# RDA5981C.net
KiCad netlist of a schematic drawn in Altium Designer
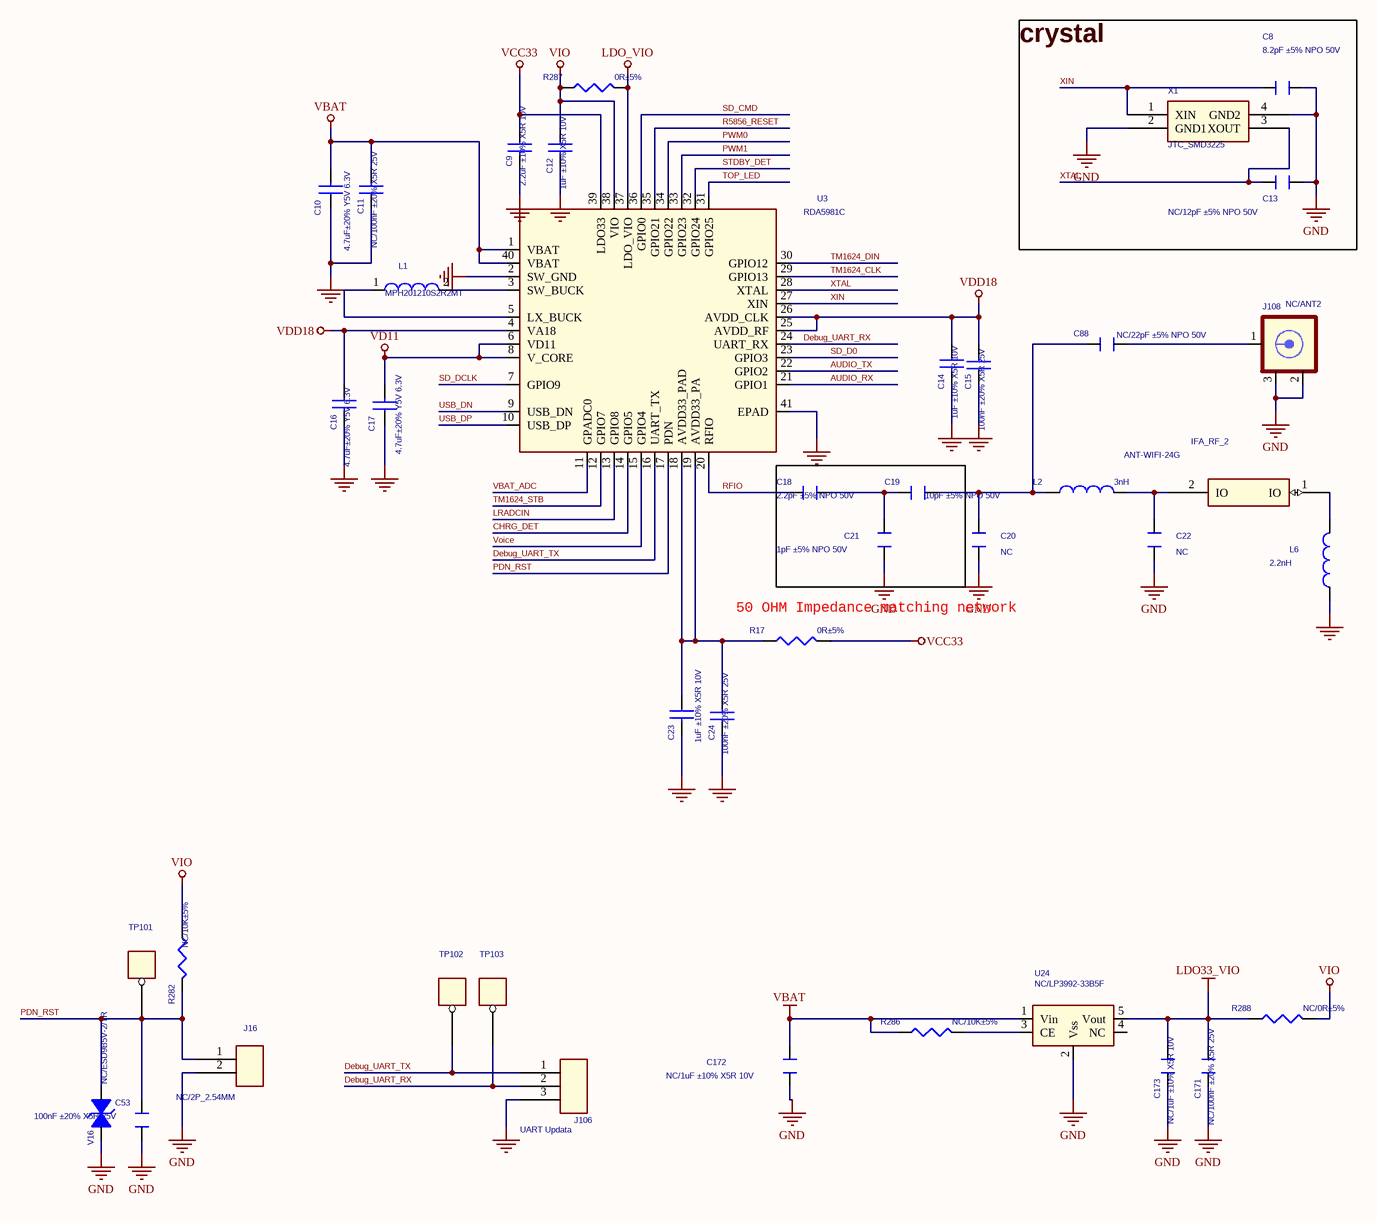
[diagram p0: RDA5981C.SchDoc]

(export (version "E")
  (design (tool "Eeschema 10.0.6"))
  (components
    (comp (ref "C8")
      (value "8.2pF ±5% NPO 50V")
      (footprint "C0402")
      (libsource (lib "*") (part "CAPACITOR_0_Dup4"))
    )
    (comp (ref "C9")
      (value "2.2uF ±10% X5R 10V")
      (footprint "C0402")
      (libsource (lib "*") (part "CAP NP_Dup6"))
    )
    (comp (ref "C10")
      (value "4.7uF±20% Y5V 6.3V")
      (footprint "C0402")
      (libsource (lib "*") (part "CAP NP_Dup4"))
    )
    (comp (ref "C11")
      (value "NC/100nF ±20% X5R 25V")
      (footprint "C0402")
      (libsource (lib "*") (part "CAP NP_Dup5"))
    )
    (comp (ref "C12")
      (value "1uF ±10% X5R 10V")
      (footprint "C0402")
      (libsource (lib "*") (part "CAP NP_Dup6"))
    )
    (comp (ref "C13")
      (value "NC/12pF ±5% NPO 50V")
      (footprint "C0402")
      (libsource (lib "*") (part "CAPACITOR_0_Dup4"))
    )
    (comp (ref "C14")
      (value "1uF ±10% X5R 10V")
      (footprint "C0402")
      (libsource (lib "*") (part "CAP NP_Dup6"))
    )
    (comp (ref "C15")
      (value "100nF ±20% X5R 25V")
      (footprint "C0402")
      (libsource (lib "*") (part "CAP NP_Dup5"))
    )
    (comp (ref "C16")
      (value "4.7uF±20% Y5V 6.3V")
      (footprint "C0402")
      (libsource (lib "*") (part "CAP NP_Dup6"))
    )
    (comp (ref "C17")
      (value "4.7uF±20% Y5V 6.3V")
      (footprint "C0402")
      (libsource (lib "*") (part "CAP NP_Dup4"))
    )
    (comp (ref "C18")
      (value "2.2pF ±5% NPO 50V")
      (footprint "C0402")
      (libsource (lib "*") (part "CAPACITOR_Dup2"))
    )
    (comp (ref "C19")
      (value "10pF ±5% NPO 50V")
      (footprint "C0402")
      (libsource (lib "*") (part "CAPACITOR_Dup2"))
    )
    (comp (ref "C20") (value "NC") (footprint "C0402") (libsource (lib "*") (part "CAPACITOR_0_Dup4")))
    (comp (ref "C21")
      (value "1pF ±5% NPO 50V")
      (footprint "C0402")
      (libsource (lib "*") (part "CAPACITOR_0_Dup4"))
    )
    (comp (ref "C22") (value "NC") (footprint "C0402") (libsource (lib "*") (part "CAPACITOR_0_Dup4")))
    (comp (ref "C23")
      (value "1uF ±10% X5R 10V")
      (footprint "C0402")
      (libsource (lib "*") (part "CAP NP_Dup6"))
    )
    (comp (ref "C24")
      (value "100nF ±20% X5R 25V")
      (footprint "C0402")
      (libsource (lib "*") (part "CAP NP_Dup5"))
    )
    (comp (ref "C53")
      (value "100nF ±20% X5R 25V")
      (footprint "C0402")
      (libsource (lib "*") (part "CAPACITOR_0_Dup4"))
    )
    (comp (ref "C88")
      (value "NC/22pF ±5% NPO 50V")
      (footprint "C0402")
      (libsource (lib "*") (part "CAPACITOR_Dup2"))
    )
    (comp (ref "C171")
      (value "NC/100nF ±20% X5R 25V")
      (footprint "C0402")
      (libsource (lib "*") (part "CAPACITOR_Dup2"))
    )
    (comp (ref "C172")
      (value "NC/1uF ±10% X5R 10V")
      (footprint "C0402")
      (libsource (lib "*") (part "CAPACITOR_Dup2"))
    )
    (comp (ref "C173")
      (value "NC/1uF ±10% X5R 10V")
      (footprint "C0402")
      (libsource (lib "*") (part "CAPACITOR_Dup2"))
    )
    (comp (ref "IFA_RF_2")
      (value "ANT-WIFI-24G")
      (footprint "IFA_RF_1")
      (libsource (lib "*") (part "ANT-25G-R-CB_0"))
    )
    (comp (ref "J16") (value "NC/2P_2.54MM") (footprint "SIP100-2P") (libsource (lib "*") (part "CON4_1")))
    (comp (ref "J106") (value "UART Updata") (footprint "SIP100-3P") (libsource (lib "*") (part "CON3")))
    (comp (ref "J108") (value "NC/ANT2") (footprint "ANT") (libsource (lib "*") (part "SMA/RF_0")))
    (comp (ref "L1")
      (value "MPH201210S2R2MT")
      (footprint "L0805")
      (description "RoHS Power Inductor 22uH 300mA H<1.8MM,CD32")
      (libsource (lib "*") (part "INDUCTOR"))
    )
    (comp (ref "L2")
      (value "3nH")
      (footprint "L0402")
      (fields (field (name "PART_NUMBER") "L42-0201S3N320ACX0"))
      (libsource (lib "*") (part "INDUCTOR_Dup1"))
    )
    (comp (ref "L6")
      (value "2.2nH")
      (footprint "L0402")
      (fields (field (name "PART_NUMBER") "L42-0201S3N320ACX0"))
      (libsource (lib "*") (part "INDUCTOR_Dup1"))
    )
    (comp (ref "R17") (value "0R±5%") (footprint "R0402") (libsource (lib "*") (part "R_Dup2")))
    (comp (ref "R282") (value "NC/10K±5%") (footprint "R0402") (libsource (lib "*") (part "R_Dup2")))
    (comp (ref "R286") (value "NC/10K±5%") (footprint "R0402") (libsource (lib "*") (part "R_Dup3")))
    (comp (ref "R287") (value "0R±5%") (footprint "R0402") (libsource (lib "*") (part "R_Dup3")))
    (comp (ref "R288") (value "NC/0R±5%") (footprint "R0402") (libsource (lib "*") (part "R_Dup3")))
    (comp (ref "TP101")
      (value "TP25RD")
      (footprint "TPC")
      (description "PAD_SM;TEST;0.025 ROUND")
      (fields (field (name "PART NUMBER") "G500-0000506"))
      (libsource (lib "*") (part "TEST_POINT"))
    )
    (comp (ref "TP102")
      (value "TP25RD")
      (footprint "TPC")
      (description "PAD_SM;TEST;0.025 ROUND")
      (fields (field (name "PART NUMBER") "G500-0000506"))
      (libsource (lib "*") (part "TEST_POINT"))
    )
    (comp (ref "TP103")
      (value "TP25RD")
      (footprint "TPC")
      (description "PAD_SM;TEST;0.025 ROUND")
      (fields (field (name "PART NUMBER") "G500-0000506"))
      (libsource (lib "*") (part "TEST_POINT"))
    )
    (comp (ref "U3")
      (value "RDA5981C")
      (footprint "QFN40-5X5-T1.0-RDA5981C")
      (libsource (lib "*") (part "RDA5981C_0"))
    )
    (comp (ref "U24")
      (value "NC/LP3992-33B5F")
      (footprint "SOT23-6")
      (libsource (lib "*") (part "RT9266PE_12"))
    )
    (comp (ref "V16")
      (value "NC/ESD9B5V-2/TR")
      (footprint "ESD0402")
      (description "Mutilayer Varistor,,5.5V,10PF")
      (fields (field (name "MANUFACTURER") "Inpaq") (field (name "PART_NUMBER") "EB3.100NV05402A"))
      (libsource (lib "*") (part "Varistor"))
    )
    (comp (ref "X1")
      (value "JTC_SMD3225")
      (footprint "SMD_3225")
      (description "Crystal 24MHz 20pF 10ppm  -30 to +85")
      (fields (field (name "PART NUMBER") "7M24000004"))
      (libsource (lib "*") (part "CRYSTAL-4_0"))
    )
  )
  (nets
    (net (code "1") (name "/AUDIO_RX") (class "Default")
      (node (ref "U3") (pin "21") (pinfunction "GPIO1_21") (pintype "passive"))
    )
    (net (code "2") (name "/AUDIO_TX") (class "Default")
      (node (ref "U3") (pin "22") (pinfunction "GPIO2_22") (pintype "passive"))
    )
    (net (code "3") (name "/CHRG_DET") (class "Default")
      (node (ref "U3") (pin "14") (pinfunction "GPIO5_14") (pintype "passive"))
    )
    (net (code "4") (name "/Debug_UART_RX") (class "Default")
      (node (ref "J106") (pin "2") (pinfunction "2_2") (pintype "passive"))
      (node (ref "TP103") (pin "1") (pinfunction "TP1_1") (pintype "passive"))
      (node (ref "U3") (pin "24") (pinfunction "UART_RX_24") (pintype "passive"))
    )
    (net (code "5") (name "/Debug_UART_TX") (class "Default")
      (node (ref "J106") (pin "1") (pinfunction "1_1") (pintype "passive"))
      (node (ref "TP102") (pin "1") (pinfunction "TP1_1") (pintype "passive"))
      (node (ref "U3") (pin "16") (pinfunction "UART_TX_16") (pintype "passive"))
    )
    (net (code "6") (name "/LRADCIN") (class "Default")
      (node (ref "U3") (pin "13") (pinfunction "GPIO8_13") (pintype "passive"))
    )
    (net (code "7") (name "/PDN_RST") (class "Default")
      (node (ref "C53") (pin "2") (pinfunction "2_2") (pintype "passive"))
      (node (ref "J16") (pin "1") (pinfunction "1_1") (pintype "passive"))
      (node (ref "R282") (pin "2") (pinfunction "2_2") (pintype "passive"))
      (node (ref "TP101") (pin "1") (pinfunction "TP1_1") (pintype "passive"))
      (node (ref "U3") (pin "17") (pinfunction "PDN_17") (pintype "passive"))
      (node (ref "V16") (pin "1") (pinfunction "I/O1_1") (pintype "passive"))
    )
    (net (code "8") (name "/PWM0") (class "Default")
      (node (ref "U3") (pin "34") (pinfunction "GPIO22_34") (pintype "passive"))
    )
    (net (code "9") (name "/PWM1") (class "Default")
      (node (ref "U3") (pin "33") (pinfunction "GPIO23_33") (pintype "passive"))
    )
    (net (code "10") (name "/R5856_RESET") (class "Default")
      (node (ref "U3") (pin "35") (pinfunction "GPIO21_35") (pintype "passive"))
    )
    (net (code "11") (name "/RFIO") (class "Default")
      (node (ref "C18") (pin "2") (pinfunction "2_2") (pintype "passive"))
      (node (ref "U3") (pin "20") (pinfunction "RFIO_20") (pintype "passive"))
    )
    (net (code "12") (name "/SD_CMD") (class "Default")
      (node (ref "U3") (pin "36") (pinfunction "GPIO0_36") (pintype "passive"))
    )
    (net (code "13") (name "/SD_D0") (class "Default")
      (node (ref "U3") (pin "23") (pinfunction "GPIO3_23") (pintype "passive"))
    )
    (net (code "14") (name "/SD_DCLK") (class "Default")
      (node (ref "U3") (pin "7") (pinfunction "GPIO9_7") (pintype "passive"))
    )
    (net (code "15") (name "/STDBY_DET") (class "Default")
      (node (ref "U3") (pin "32") (pinfunction "GPIO24_32") (pintype "passive"))
    )
    (net (code "16") (name "/TM1624_CLK") (class "Default")
      (node (ref "U3") (pin "29") (pinfunction "GPIO13_29") (pintype "passive"))
    )
    (net (code "17") (name "/TM1624_DIN") (class "Default")
      (node (ref "U3") (pin "30") (pinfunction "GPIO12_30") (pintype "passive"))
    )
    (net (code "18") (name "/TM1624_STB") (class "Default")
      (node (ref "U3") (pin "12") (pinfunction "GPIO7_12") (pintype "passive"))
    )
    (net (code "19") (name "/TOP_LED") (class "Default")
      (node (ref "U3") (pin "31") (pinfunction "GPIO25_31") (pintype "passive"))
    )
    (net (code "20") (name "/USB_DN") (class "Default")
      (node (ref "U3") (pin "9") (pinfunction "USB_DN_9") (pintype "passive"))
    )
    (net (code "21") (name "/USB_DP") (class "Default")
      (node (ref "U3") (pin "10") (pinfunction "USB_DP_10") (pintype "passive"))
    )
    (net (code "22") (name "/VBAT_ADC") (class "Default")
      (node (ref "U3") (pin "11") (pinfunction "GPADC0_11") (pintype "passive"))
    )
    (net (code "23") (name "/Voice") (class "Default")
      (node (ref "U3") (pin "15") (pinfunction "GPIO4_15") (pintype "passive"))
    )
    (net (code "24") (name "/XIN") (class "Default")
      (node (ref "C8") (pin "2") (pinfunction "2_2") (pintype "passive"))
      (node (ref "U3") (pin "27") (pinfunction "XIN_27") (pintype "passive"))
      (node (ref "X1") (pin "1") (pinfunction "XIN_1") (pintype "passive"))
    )
    (net (code "25") (name "/XTAL") (class "Default")
      (node (ref "C13") (pin "2") (pinfunction "2_2") (pintype "passive"))
      (node (ref "U3") (pin "28") (pinfunction "XTAL_28") (pintype "passive"))
      (node (ref "X1") (pin "3") (pinfunction "XOUT_3") (pintype "passive"))
    )
    (net (code "26") (name "GND") (class "Default")
      (node (ref "C10") (pin "1") (pinfunction "1_1") (pintype "passive"))
      (node (ref "C11") (pin "1") (pinfunction "1_1") (pintype "passive"))
      (node (ref "C12") (pin "2") (pinfunction "2_2") (pintype "passive"))
      (node (ref "C13") (pin "1") (pinfunction "1_1") (pintype "passive"))
      (node (ref "C14") (pin "2") (pinfunction "2_2") (pintype "passive"))
      (node (ref "C15") (pin "1") (pinfunction "1_1") (pintype "passive"))
      (node (ref "C16") (pin "2") (pinfunction "2_2") (pintype "passive"))
      (node (ref "C17") (pin "1") (pinfunction "1_1") (pintype "passive"))
      (node (ref "C171") (pin "1") (pinfunction "1_1") (pintype "passive"))
      (node (ref "C172") (pin "1") (pinfunction "1_1") (pintype "passive"))
      (node (ref "C173") (pin "1") (pinfunction "1_1") (pintype "passive"))
      (node (ref "C20") (pin "2") (pinfunction "2_2") (pintype "passive"))
      (node (ref "C21") (pin "2") (pinfunction "2_2") (pintype "passive"))
      (node (ref "C22") (pin "2") (pinfunction "2_2") (pintype "passive"))
      (node (ref "C23") (pin "2") (pinfunction "2_2") (pintype "passive"))
      (node (ref "C24") (pin "1") (pinfunction "1_1") (pintype "passive"))
      (node (ref "C53") (pin "1") (pinfunction "1_1") (pintype "passive"))
      (node (ref "C8") (pin "1") (pinfunction "1_1") (pintype "passive"))
      (node (ref "C9") (pin "2") (pinfunction "2_2") (pintype "passive"))
      (node (ref "J106") (pin "3") (pinfunction "3_3") (pintype "passive"))
      (node (ref "J108") (pin "2") (pinfunction "SHIELD1_2") (pintype "passive"))
      (node (ref "J108") (pin "3") (pinfunction "SHIELD2_3") (pintype "passive"))
      (node (ref "J16") (pin "2") (pinfunction "2_2") (pintype "passive"))
      (node (ref "L6") (pin "1") (pinfunction "1_1") (pintype "passive"))
      (node (ref "U24") (pin "2") (pinfunction "Vss_2") (pintype "passive"))
      (node (ref "U3") (pin "2") (pinfunction "SW_GND_2") (pintype "passive"))
      (node (ref "U3") (pin "41") (pinfunction "EPAD_41") (pintype "passive"))
      (node (ref "V16") (pin "2") (pinfunction "I/O2_2") (pintype "passive"))
      (node (ref "X1") (pin "2") (pinfunction "GND1_2") (pintype "power_in"))
      (node (ref "X1") (pin "4") (pinfunction "GND2_4") (pintype "power_in"))
    )
    (net (code "27") (name "LDO33_VIO") (class "Default")
      (node (ref "C171") (pin "2") (pinfunction "2_2") (pintype "passive"))
      (node (ref "C173") (pin "2") (pinfunction "2_2") (pintype "passive"))
      (node (ref "R288") (pin "1") (pinfunction "1_1") (pintype "passive"))
      (node (ref "U24") (pin "5") (pinfunction "Vout_5") (pintype "passive"))
    )
    (net (code "28") (name "LDO_VIO") (class "Default")
      (node (ref "R287") (pin "2") (pinfunction "2_2") (pintype "passive"))
      (node (ref "U3") (pin "37") (pinfunction "LDO_VIO_37") (pintype "passive"))
    )
    (net (code "29") (name "Net-(C18-Pad1)") (class "Default")
      (node (ref "C18") (pin "1") (pinfunction "1_1") (pintype "passive"))
      (node (ref "C19") (pin "2") (pinfunction "2_2") (pintype "passive"))
      (node (ref "C21") (pin "1") (pinfunction "1_1") (pintype "passive"))
    )
    (net (code "30") (name "Net-(C19-Pad1)") (class "Default")
      (node (ref "C19") (pin "1") (pinfunction "1_1") (pintype "passive"))
      (node (ref "C20") (pin "1") (pinfunction "1_1") (pintype "passive"))
      (node (ref "C88") (pin "2") (pinfunction "2_2") (pintype "passive"))
      (node (ref "L2") (pin "1") (pinfunction "1_1") (pintype "passive"))
    )
    (net (code "31") (name "Net-(C22-Pad1)") (class "Default")
      (node (ref "C22") (pin "1") (pinfunction "1_1") (pintype "passive"))
      (node (ref "IFA_RF_2") (pin "2") (pinfunction "IO_2") (pintype "passive"))
      (node (ref "L2") (pin "2") (pinfunction "2_2") (pintype "passive"))
    )
    (net (code "32") (name "Net-(IFA_RF_2-IO-Pad1)") (class "Default")
      (node (ref "IFA_RF_2") (pin "1") (pinfunction "IO_1") (pintype "bidirectional"))
      (node (ref "L6") (pin "2") (pinfunction "2_2") (pintype "passive"))
    )
    (net (code "33") (name "Net-(J108-CENTER)") (class "Default")
      (node (ref "C88") (pin "1") (pinfunction "1_1") (pintype "passive"))
      (node (ref "J108") (pin "1") (pinfunction "CENTER_1") (pintype "passive"))
    )
    (net (code "34") (name "Net-(U3-AVDD33_PA)") (class "Default")
      (node (ref "C23") (pin "1") (pinfunction "1_1") (pintype "passive"))
      (node (ref "C24") (pin "2") (pinfunction "2_2") (pintype "passive"))
      (node (ref "R17") (pin "1") (pinfunction "1_1") (pintype "passive"))
      (node (ref "U3") (pin "18") (pinfunction "AVDD33_PAD_18") (pintype "passive"))
      (node (ref "U3") (pin "19") (pinfunction "AVDD33_PA_19") (pintype "passive"))
    )
    (net (code "35") (name "Net-(U3-LX_BUCK)") (class "Default")
      (node (ref "L1") (pin "1") (pinfunction "1_1") (pintype "passive"))
      (node (ref "U3") (pin "5") (pinfunction "LX_BUCK_5") (pintype "passive"))
    )
    (net (code "36") (name "Net-(U3-SW_BUCK)") (class "Default")
      (node (ref "L1") (pin "2") (pinfunction "2_2") (pintype "passive"))
      (node (ref "U3") (pin "3") (pinfunction "SW_BUCK_3") (pintype "passive"))
    )
    (net (code "37") (name "Net-(U24-CE)") (class "Default")
      (node (ref "R286") (pin "2") (pinfunction "2_2") (pintype "passive"))
      (node (ref "U24") (pin "3") (pinfunction "CE_3") (pintype "passive"))
    )
    (net (code "38") (name "VBAT") (class "Default")
      (node (ref "C10") (pin "2") (pinfunction "2_2") (pintype "passive"))
      (node (ref "C11") (pin "2") (pinfunction "2_2") (pintype "passive"))
      (node (ref "C172") (pin "2") (pinfunction "2_2") (pintype "passive"))
      (node (ref "R286") (pin "1") (pinfunction "1_1") (pintype "passive"))
      (node (ref "U24") (pin "1") (pinfunction "Vin_1") (pintype "passive"))
      (node (ref "U3") (pin "1") (pinfunction "VBAT_1") (pintype "passive"))
      (node (ref "U3") (pin "40") (pinfunction "VBAT_40") (pintype "passive"))
    )
    (net (code "39") (name "VCC33") (class "Default")
      (node (ref "C9") (pin "1") (pinfunction "1_1") (pintype "passive"))
      (node (ref "R17") (pin "2") (pinfunction "2_2") (pintype "passive"))
      (node (ref "U3") (pin "39") (pinfunction "LDO33_39") (pintype "passive"))
    )
    (net (code "40") (name "VD11") (class "Default")
      (node (ref "C17") (pin "2") (pinfunction "2_2") (pintype "passive"))
      (node (ref "U3") (pin "6") (pinfunction "VD11_6") (pintype "passive"))
      (node (ref "U3") (pin "8") (pinfunction "V_CORE_8") (pintype "passive"))
    )
    (net (code "41") (name "VDD18") (class "Default")
      (node (ref "C14") (pin "1") (pinfunction "1_1") (pintype "passive"))
      (node (ref "C15") (pin "2") (pinfunction "2_2") (pintype "passive"))
      (node (ref "C16") (pin "1") (pinfunction "1_1") (pintype "passive"))
      (node (ref "U3") (pin "25") (pinfunction "AVDD_RF_25") (pintype "passive"))
      (node (ref "U3") (pin "26") (pinfunction "AVDD_CLK_26") (pintype "passive"))
      (node (ref "U3") (pin "4") (pinfunction "VA18_4") (pintype "passive"))
    )
    (net (code "42") (name "VIO") (class "Default")
      (node (ref "C12") (pin "1") (pinfunction "1_1") (pintype "passive"))
      (node (ref "R282") (pin "1") (pinfunction "1_1") (pintype "passive"))
      (node (ref "R287") (pin "1") (pinfunction "1_1") (pintype "passive"))
      (node (ref "R288") (pin "2") (pinfunction "2_2") (pintype "passive"))
      (node (ref "U3") (pin "38") (pinfunction "VIO_38") (pintype "passive"))
    )
    (net (code "43") (name "unconnected-(U24-NC-Pad4)") (class "Default")
      (node (ref "U24") (pin "4") (pinfunction "NC_4") (pintype "passive"))
    )
  )
)
